# Y-babies_--_PicAxe.net
KiCad netlist of a schematic drawn in EAGLE
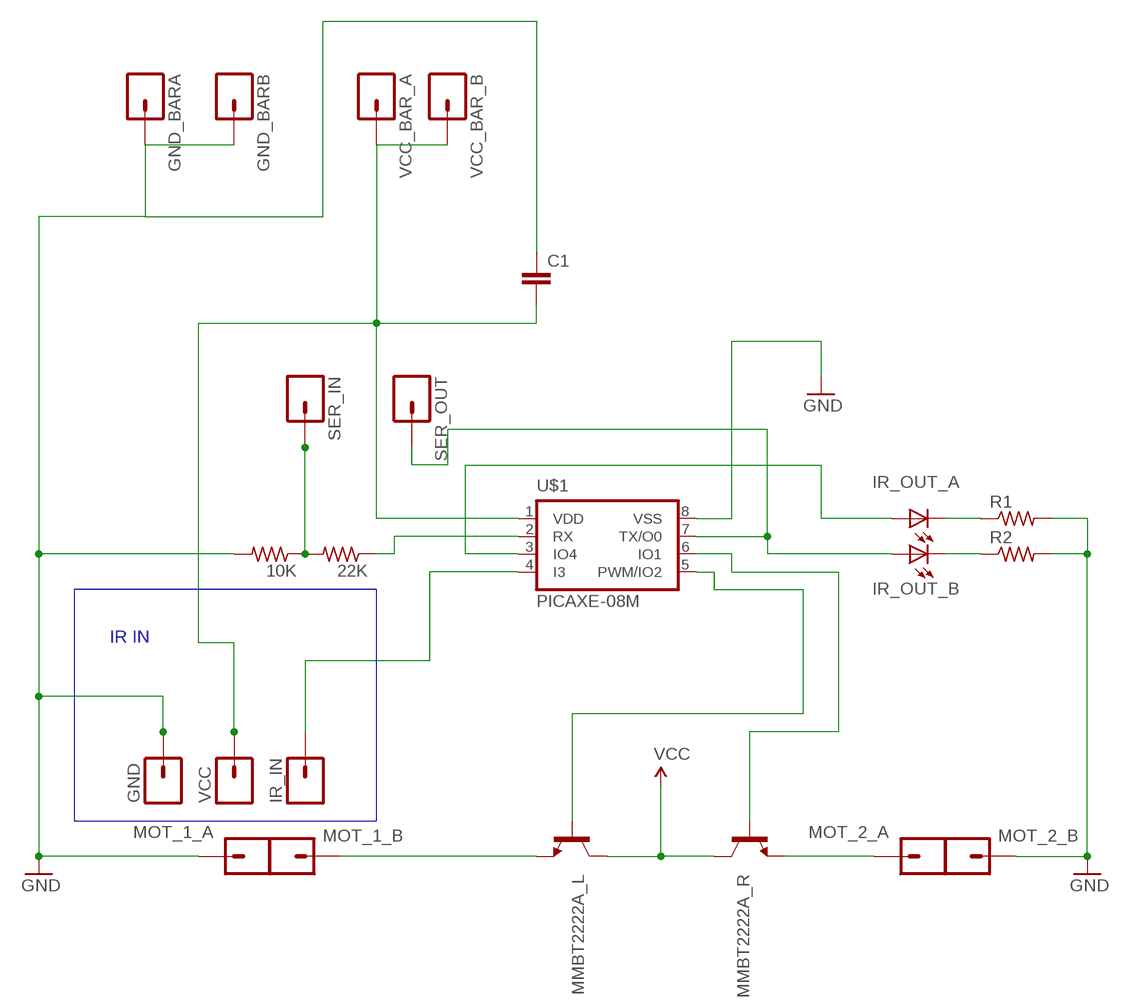
[diagram p0: schematic, sheet 1]

(export (version "E")
  (design (tool "Eeschema 10.0.6"))
  (components
    (comp (ref "10K")
      (value "R-US_R0805W")
      (footprint "eagle-import:R0805W")
      (libsource (lib "eagle-import") (part "R-US_R0805W"))
    )
    (comp (ref "22K")
      (value "R-US_R0805W")
      (footprint "eagle-import:R0805W")
      (libsource (lib "eagle-import") (part "R-US_R0805W"))
    )
    (comp (ref "C1")
      (value "CAPPTH1")
      (footprint "eagle-import:CAP-PTH-5MM")
      (libsource (lib "eagle-import") (part "CAPPTH1"))
    )
    (comp (ref "GND")
      (value "M01PTH")
      (footprint "eagle-import:1X01")
      (libsource (lib "eagle-import") (part "M01PTH"))
    )
    (comp (ref "GND_BARA")
      (value "M01PTH")
      (footprint "eagle-import:1X01")
      (libsource (lib "eagle-import") (part "M01PTH"))
    )
    (comp (ref "GND_BARB")
      (value "M01PTH")
      (footprint "eagle-import:1X01")
      (libsource (lib "eagle-import") (part "M01PTH"))
    )
    (comp (ref "IR_IN")
      (value "M01PTH")
      (footprint "eagle-import:1X01")
      (libsource (lib "eagle-import") (part "M01PTH"))
    )
    (comp (ref "IR_OUT_A")
      (value "LED3MM")
      (footprint "eagle-import:LED3MM")
      (libsource (lib "eagle-import") (part "LED3MM"))
    )
    (comp (ref "IR_OUT_B")
      (value "LED3MM")
      (footprint "eagle-import:LED3MM")
      (libsource (lib "eagle-import") (part "LED3MM"))
    )
    (comp (ref "MMBT2222A_L")
      (value "TRANSISTOR_NPNSOT23")
      (footprint "eagle-import:SOT23")
      (libsource (lib "eagle-import") (part "TRANSISTOR_NPNSOT23"))
    )
    (comp (ref "MMBT2222A_R")
      (value "TRANSISTOR_NPNSOT23")
      (footprint "eagle-import:SOT23")
      (libsource (lib "eagle-import") (part "TRANSISTOR_NPNSOT23"))
    )
    (comp (ref "MOT_1_A")
      (value "M01SMD-4.5X1.5")
      (footprint "eagle-import:PAD-1.5X4.5")
      (libsource (lib "eagle-import") (part "M01SMD-4.5X1.5"))
    )
    (comp (ref "MOT_1_B")
      (value "M01SMD-4.5X1.5")
      (footprint "eagle-import:PAD-1.5X4.5")
      (libsource (lib "eagle-import") (part "M01SMD-4.5X1.5"))
    )
    (comp (ref "MOT_2_A")
      (value "M01SMD-4.5X1.5")
      (footprint "eagle-import:PAD-1.5X4.5")
      (libsource (lib "eagle-import") (part "M01SMD-4.5X1.5"))
    )
    (comp (ref "MOT_2_B")
      (value "M01SMD-4.5X1.5")
      (footprint "eagle-import:PAD-1.5X4.5")
      (libsource (lib "eagle-import") (part "M01SMD-4.5X1.5"))
    )
    (comp (ref "R1")
      (value "R-US_R0805W")
      (footprint "eagle-import:R0805W")
      (libsource (lib "eagle-import") (part "R-US_R0805W"))
    )
    (comp (ref "R2")
      (value "R-US_R0805W")
      (footprint "eagle-import:R0805W")
      (libsource (lib "eagle-import") (part "R-US_R0805W"))
    )
    (comp (ref "SER_IN")
      (value "M01PTH")
      (footprint "eagle-import:1X01")
      (libsource (lib "eagle-import") (part "M01PTH"))
    )
    (comp (ref "SER_OUT")
      (value "M01PTH")
      (footprint "eagle-import:1X01")
      (libsource (lib "eagle-import") (part "M01PTH"))
    )
    (comp (ref "U$1")
      (value "PICAXE-08M")
      (footprint "eagle-import:DIL8")
      (libsource (lib "eagle-import") (part "PICAXE-08M"))
    )
    (comp (ref "VCC")
      (value "M01PTH")
      (footprint "eagle-import:1X01")
      (libsource (lib "eagle-import") (part "M01PTH"))
    )
    (comp (ref "VCC_BAR_A")
      (value "M01PTH")
      (footprint "eagle-import:1X01")
      (libsource (lib "eagle-import") (part "M01PTH"))
    )
    (comp (ref "VCC_BAR_B")
      (value "M01PTH")
      (footprint "eagle-import:1X01")
      (libsource (lib "eagle-import") (part "M01PTH"))
    )
  )
  (nets
    (net (code "1") (name "GND") (class "Default")
      (node (ref "10K") (pin "2") (pinfunction "2_2") (pintype "passive"))
      (node (ref "C1") (pin "1") (pinfunction "1_1") (pintype "passive"))
      (node (ref "GND") (pin "1") (pinfunction "1_1") (pintype "passive"))
      (node (ref "GND_BARA") (pin "1") (pinfunction "1_1") (pintype "passive"))
      (node (ref "GND_BARB") (pin "1") (pinfunction "1_1") (pintype "passive"))
      (node (ref "MOT_1_A") (pin "P$1") (pinfunction "1_P$1") (pintype "passive"))
      (node (ref "MOT_2_B") (pin "P$1") (pinfunction "1_P$1") (pintype "passive"))
      (node (ref "R1") (pin "2") (pinfunction "2_2") (pintype "passive"))
      (node (ref "R2") (pin "2") (pinfunction "2_2") (pintype "passive"))
      (node (ref "U$1") (pin "8") (pinfunction "VSS_8") (pintype "power_in"))
    )
    (net (code "2") (name "Net-(10K-Pad1)") (class "Default")
      (node (ref "10K") (pin "1") (pinfunction "1_1") (pintype "passive"))
      (node (ref "22K") (pin "2") (pinfunction "2_2") (pintype "passive"))
      (node (ref "SER_IN") (pin "1") (pinfunction "1_1") (pintype "passive"))
    )
    (net (code "3") (name "Net-(IR_OUT_A-C)") (class "Default")
      (node (ref "IR_OUT_A") (pin "K") (pinfunction "C_K") (pintype "passive"))
      (node (ref "R1") (pin "1") (pinfunction "1_1") (pintype "passive"))
    )
    (net (code "4") (name "Net-(IR_OUT_B-C)") (class "Default")
      (node (ref "IR_OUT_B") (pin "K") (pinfunction "C_K") (pintype "passive"))
      (node (ref "R2") (pin "1") (pinfunction "1_1") (pintype "passive"))
    )
    (net (code "5") (name "Net-(MMBT2222A_L-B)") (class "Default")
      (node (ref "MMBT2222A_L") (pin "1") (pinfunction "B_1") (pintype "passive"))
      (node (ref "U$1") (pin "5") (pinfunction "PWM/IO2_5") (pintype "bidirectional"))
    )
    (net (code "6") (name "Net-(MMBT2222A_L-E)") (class "Default")
      (node (ref "MMBT2222A_L") (pin "2") (pinfunction "E_2") (pintype "passive"))
      (node (ref "MOT_1_B") (pin "P$1") (pinfunction "1_P$1") (pintype "passive"))
    )
    (net (code "7") (name "Net-(MMBT2222A_R-B)") (class "Default")
      (node (ref "MMBT2222A_R") (pin "1") (pinfunction "B_1") (pintype "passive"))
      (node (ref "U$1") (pin "6") (pinfunction "IO1_6") (pintype "bidirectional"))
    )
    (net (code "8") (name "Net-(MMBT2222A_R-E)") (class "Default")
      (node (ref "MMBT2222A_R") (pin "2") (pinfunction "E_2") (pintype "passive"))
      (node (ref "MOT_2_A") (pin "P$1") (pinfunction "1_P$1") (pintype "passive"))
    )
    (net (code "9") (name "Net-(U$1-I3)") (class "Default")
      (node (ref "IR_IN") (pin "1") (pinfunction "1_1") (pintype "passive"))
      (node (ref "U$1") (pin "4") (pinfunction "I3_4") (pintype "input"))
    )
    (net (code "10") (name "Net-(U$1-IO4)") (class "Default")
      (node (ref "IR_OUT_A") (pin "A") (pinfunction "A_A") (pintype "passive"))
      (node (ref "U$1") (pin "3") (pinfunction "IO4_3") (pintype "bidirectional"))
    )
    (net (code "11") (name "Net-(U$1-RX)") (class "Default")
      (node (ref "22K") (pin "1") (pinfunction "1_1") (pintype "passive"))
      (node (ref "U$1") (pin "2") (pinfunction "RX_2") (pintype "input"))
    )
    (net (code "12") (name "Net-(U$1-TX{slash}O0)") (class "Default")
      (node (ref "IR_OUT_B") (pin "A") (pinfunction "A_A") (pintype "passive"))
      (node (ref "SER_OUT") (pin "1") (pinfunction "1_1") (pintype "passive"))
      (node (ref "U$1") (pin "7") (pinfunction "TX/O0_7") (pintype "output"))
    )
    (net (code "13") (name "VCC") (class "Default")
      (node (ref "C1") (pin "2") (pinfunction "2_2") (pintype "passive"))
      (node (ref "MMBT2222A_L") (pin "3") (pinfunction "C_3") (pintype "passive"))
      (node (ref "MMBT2222A_R") (pin "3") (pinfunction "C_3") (pintype "passive"))
      (node (ref "U$1") (pin "1") (pinfunction "VDD_1") (pintype "power_in"))
      (node (ref "VCC") (pin "1") (pinfunction "1_1") (pintype "passive"))
      (node (ref "VCC_BAR_A") (pin "1") (pinfunction "1_1") (pintype "passive"))
      (node (ref "VCC_BAR_B") (pin "1") (pinfunction "1_1") (pintype "passive"))
    )
  )
)
